# LEMC.net
KiCad netlist of a schematic drawn in Altium Designer
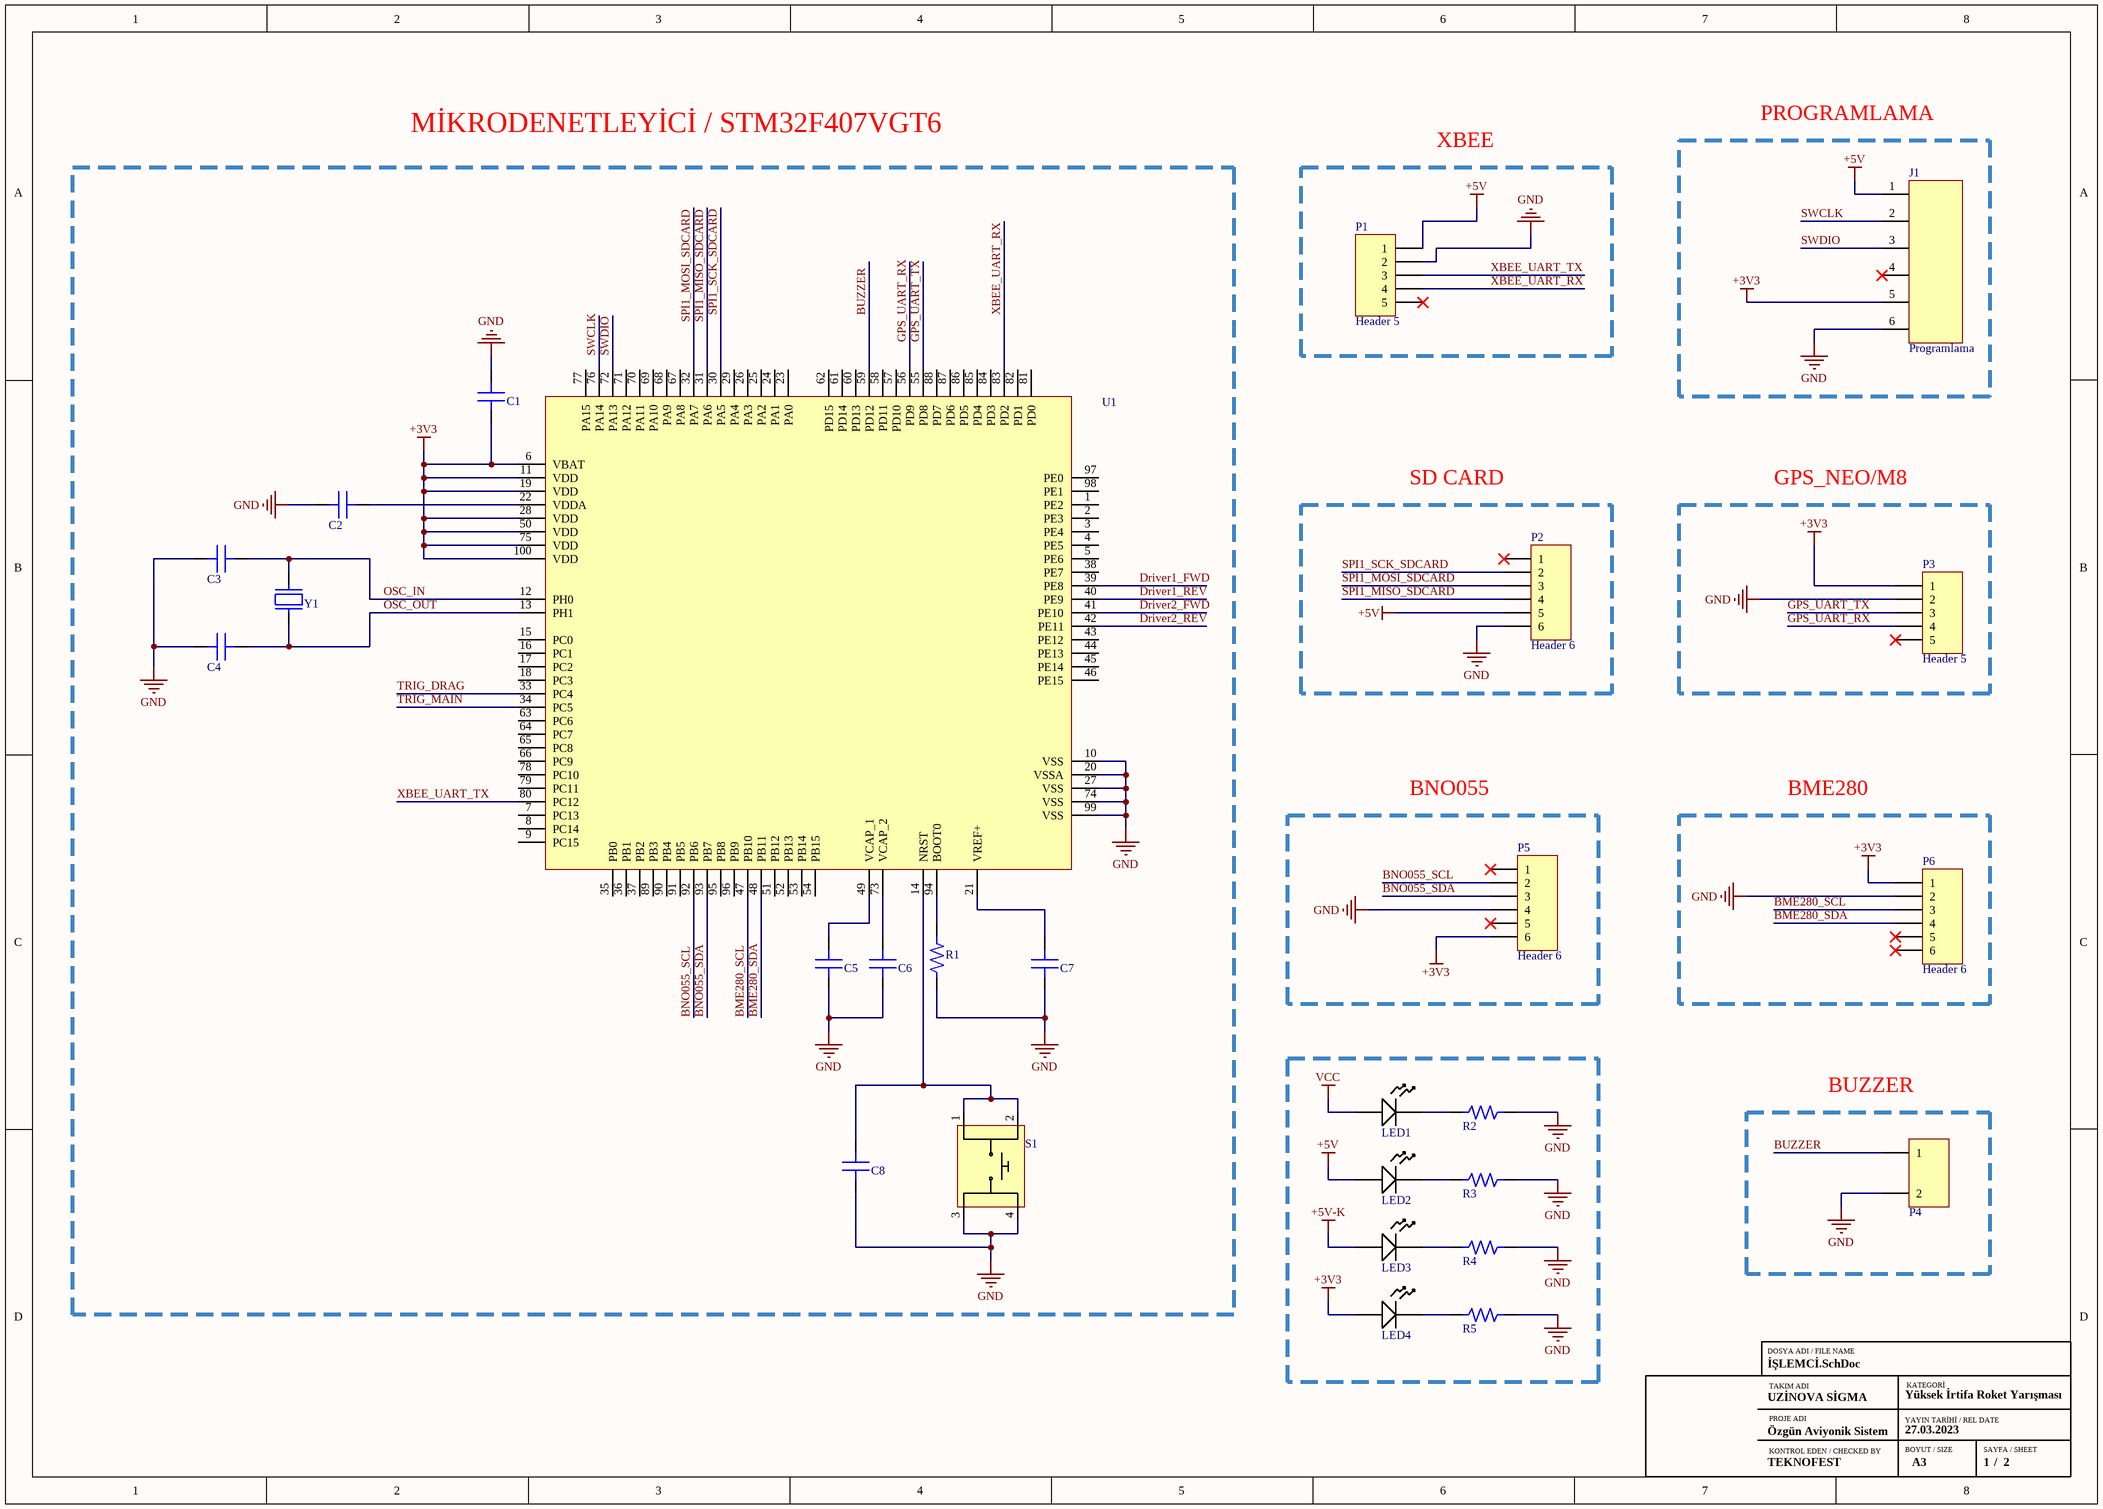
[diagram p0: İŞLEMCİ.SchDoc]

(export (version "E")
  (design (tool "Eeschema 10.0.6"))
  (components
    (comp (ref "C1")
      (value "CAP CER 1uF 0805")
      (footprint "CAP_0805")
      (libsource (lib "ROKET_LIBRARY") (part "CAP CER 1uF 0805"))
    )
    (comp (ref "C2")
      (value "CAP CER 10nF 0805")
      (footprint "CAP_0805")
      (libsource (lib "ROKET_LIBRARY") (part "CAP CER 10nF 0805"))
    )
    (comp (ref "C3")
      (value "CAP CER 20pF 0805")
      (footprint "CAP_0805")
      (libsource (lib "ROKET_LIBRARY") (part "CAP CER 20pF 0805"))
    )
    (comp (ref "C4")
      (value "CAP CER 20pF 0805")
      (footprint "CAP_0805")
      (libsource (lib "ROKET_LIBRARY") (part "CAP CER 20pF 0805"))
    )
    (comp (ref "C5")
      (value "CAP CER 2.2uF 0805")
      (footprint "CAP_0805")
      (libsource (lib "ROKET_LIBRARY") (part "CAP CER 2.2uF 0805"))
    )
    (comp (ref "C6")
      (value "CAP CER 2.2uF 0805")
      (footprint "CAP_0805")
      (libsource (lib "ROKET_LIBRARY") (part "CAP CER 2.2uF 0805"))
    )
    (comp (ref "C7")
      (value "CAP CER 10nF 0805")
      (footprint "CAP_0805")
      (libsource (lib "ROKET_LIBRARY") (part "CAP CER 10nF 0805"))
    )
    (comp (ref "C8")
      (value "CAP CER 0.1uF 0805")
      (footprint "CAP_0805")
      (libsource (lib "ROKET_LIBRARY") (part "CAP CER 0.1uF 0805"))
    )
    (comp (ref "J1")
      (value "Programlama")
      (footprint "PPTC061LFBN-RC")
      (libsource (lib "ROKET_LIBRARY") (part "Programlama"))
    )
    (comp (ref "LED1")
      (value "CMD17-21VRD/TR8")
      (footprint "LED RED_0805")
      (description "LED Uni-Color Red 640nm 2-Pin SMT T/R")
      (fields (field (name "MANUFACTURER") "VCC CHML"))
      (libsource (lib "ROKET_LIBRARY") (part "LED RED"))
    )
    (comp (ref "LED2")
      (value "CMD17-21VRD/TR8")
      (footprint "LED RED_0805")
      (description "LED Uni-Color Red 640nm 2-Pin SMT T/R")
      (fields (field (name "MANUFACTURER") "VCC CHML"))
      (libsource (lib "ROKET_LIBRARY") (part "LED RED"))
    )
    (comp (ref "LED3")
      (value "CMD17-21VRD/TR8")
      (footprint "LED RED_0805")
      (description "LED Uni-Color Red 640nm 2-Pin SMT T/R")
      (fields (field (name "MANUFACTURER") "VCC CHML"))
      (libsource (lib "ROKET_LIBRARY") (part "LED RED"))
    )
    (comp (ref "LED4")
      (value "CMD17-21VRD/TR8")
      (footprint "LED RED_0805")
      (description "LED Uni-Color Red 640nm 2-Pin SMT T/R")
      (fields (field (name "MANUFACTURER") "VCC CHML"))
      (libsource (lib "ROKET_LIBRARY") (part "LED RED"))
    )
    (comp (ref "P1")
      (value "Header 5")
      (footprint "HDR1X5")
      (description "Header, 5-Pin")
      (fields (field (name "PUBLISHER") "Altium Limited"))
      (libsource (lib "Miscellaneous Connectors") (part "Header 5"))
    )
    (comp (ref "P2")
      (value "Header 6")
      (footprint "HDR1X6")
      (description "Header, 6-Pin")
      (fields (field (name "PUBLISHER") "Altium Limited"))
      (libsource (lib "Miscellaneous Connectors") (part "Header 6"))
    )
    (comp (ref "P3")
      (value "Header 5")
      (footprint "HDR1X5")
      (description "Header, 5-Pin")
      (fields (field (name "PUBLISHER") "Altium Limited"))
      (libsource (lib "") (part "Header 5_1"))
    )
    (comp (ref "P4")
      (value "Yalancı Buzzer")
      (footprint "Yalancı Buzzer")
      (libsource (lib "ROKET_LIBRARY") (part "Yalancı Buzzer"))
    )
    (comp (ref "P5")
      (value "Header 6")
      (footprint "HDR1X6")
      (description "Header, 6-Pin")
      (fields (field (name "PUBLISHER") "Altium Limited"))
      (libsource (lib "Miscellaneous Connectors") (part "Header 6"))
    )
    (comp (ref "P6")
      (value "Header 6")
      (footprint "HDR1X6")
      (description "Header, 6-Pin")
      (fields (field (name "PUBLISHER") "Altium Limited"))
      (libsource (lib "Miscellaneous Connectors") (part "Header 6"))
    )
    (comp (ref "R1")
      (value "RES 10K OHM 0805")
      (footprint "RES_0805")
      (libsource (lib "ROKET_LIBRARY") (part "RES 10K OHM 0805"))
    )
    (comp (ref "R2")
      (value "RES 470 OHM 0805")
      (footprint "RES_0805")
      (libsource (lib "ROKET_LIBRARY") (part "RES 470 OHM 0805"))
    )
    (comp (ref "R3")
      (value "RES 470 OHM 0805")
      (footprint "RES_0805")
      (libsource (lib "ROKET_LIBRARY") (part "RES 470 OHM 0805"))
    )
    (comp (ref "R4")
      (value "RES 470 OHM 0805")
      (footprint "RES_0805")
      (libsource (lib "ROKET_LIBRARY") (part "RES 470 OHM 0805"))
    )
    (comp (ref "R5")
      (value "RES 470 OHM 0805")
      (footprint "RES_0805")
      (libsource (lib "ROKET_LIBRARY") (part "RES 470 OHM 0805"))
    )
    (comp (ref "S1")
      (value "PTS815 SJG 250 SMTR LFS")
      (footprint "BUTTON")
      (description "Switch Tactile N.O. SPST Button J-Bend 0.05A 12VDC 3.92N SMD T/R")
      (fields
        (field (name "MANUFACTURER") "ITT C&K")
        (field (name "MANUFACTURER PART NUMBER") "PTS815SJG250SMTRLFS")
      )
      (libsource (lib "ROKET_LIBRARY") (part "BUTTON"))
    )
    (comp (ref "U1")
      (value "STM32F407VGT6")
      (footprint "LQFP-100")
      (description "IC MCU 32BIT 1MB FLASH 100LQFP")
      (fields (field (name "MANUFACTURER") "STMicroelectronics"))
      (libsource (lib "ROKET_LIBRARY") (part "STM32F407VGT6"))
    )
    (comp (ref "Y1")
      (value "CRYSTAL 32.7680KHZ 12.5PF SMD")
      (footprint "CRYSTAL_ABS05")
      (description "Crystal 0.032768MHz ±20ppm (Tol) 12.5pF Flexural 90000Ohm 2-Pin CSMD T/R")
      (fields
        (field (name "MANUFACTURER") "Abracon")
        (field (name "MANUFACTURER PART NUMBER") "ABS05-32.768KHZ-T")
      )
      (libsource (lib "ROKET_LIBRARY") (part "CRYSTAL"))
    )
  )
  (nets
    (net (code "1") (name "+3V3") (class "Default")
      (node (ref "C1") (pin "1") (pinfunction "1_1") (pintype "passive"))
      (node (ref "J1") (pin "5") (pintype "passive"))
      (node (ref "LED4") (pin "1") (pinfunction "1_1") (pintype "passive"))
      (node (ref "P3") (pin "1") (pinfunction "1_1") (pintype "passive"))
      (node (ref "P5") (pin "6") (pinfunction "6_6") (pintype "passive"))
      (node (ref "P6") (pin "1") (pinfunction "1_1") (pintype "passive"))
      (node (ref "U1") (pin "100") (pinfunction "VDD_100") (pintype "passive"))
      (node (ref "U1") (pin "11") (pinfunction "VDD_11") (pintype "passive"))
      (node (ref "U1") (pin "19") (pinfunction "VDD_19") (pintype "passive"))
      (node (ref "U1") (pin "28") (pinfunction "VDD_28") (pintype "passive"))
      (node (ref "U1") (pin "50") (pinfunction "VDD_50") (pintype "passive"))
      (node (ref "U1") (pin "6") (pinfunction "VBAT_6") (pintype "passive"))
      (node (ref "U1") (pin "75") (pinfunction "VDD_75") (pintype "passive"))
    )
    (net (code "2") (name "+5V") (class "Default")
      (node (ref "J1") (pin "1") (pintype "passive"))
      (node (ref "LED2") (pin "1") (pinfunction "1_1") (pintype "passive"))
      (node (ref "P1") (pin "1") (pinfunction "1_1") (pintype "passive"))
      (node (ref "P2") (pin "5") (pinfunction "5_5") (pintype "passive"))
    )
    (net (code "3") (name "+5V-K") (class "Default")
      (node (ref "LED3") (pin "1") (pinfunction "1_1") (pintype "passive"))
    )
    (net (code "4") (name "/BME280_SCL") (class "Default")
      (node (ref "P6") (pin "3") (pinfunction "3_3") (pintype "passive"))
      (node (ref "U1") (pin "47") (pinfunction "PB10_47") (pintype "passive"))
    )
    (net (code "5") (name "/BME280_SDA") (class "Default")
      (node (ref "P6") (pin "4") (pinfunction "4_4") (pintype "passive"))
      (node (ref "U1") (pin "48") (pinfunction "PB11_48") (pintype "passive"))
    )
    (net (code "6") (name "/BNO055_SCL") (class "Default")
      (node (ref "P5") (pin "2") (pinfunction "2_2") (pintype "passive"))
      (node (ref "U1") (pin "92") (pinfunction "PB6_92") (pintype "passive"))
    )
    (net (code "7") (name "/BNO055_SDA") (class "Default")
      (node (ref "P5") (pin "3") (pinfunction "3_3") (pintype "passive"))
      (node (ref "U1") (pin "93") (pinfunction "PB7_93") (pintype "passive"))
    )
    (net (code "8") (name "/BUZZER") (class "Default")
      (node (ref "P4") (pin "1") (pinfunction "1_1") (pintype "passive"))
      (node (ref "U1") (pin "59") (pinfunction "PD12_59") (pintype "passive"))
    )
    (net (code "9") (name "/Driver1_FWD") (class "Default")
      (node (ref "U1") (pin "39") (pinfunction "PE8_39") (pintype "passive"))
    )
    (net (code "10") (name "/Driver1_REV") (class "Default")
      (node (ref "U1") (pin "40") (pinfunction "PE9_40") (pintype "passive"))
    )
    (net (code "11") (name "/Driver2_FWD") (class "Default")
      (node (ref "U1") (pin "41") (pinfunction "PE10_41") (pintype "passive"))
    )
    (net (code "12") (name "/Driver2_REV") (class "Default")
      (node (ref "U1") (pin "42") (pinfunction "PE11_42") (pintype "passive"))
    )
    (net (code "13") (name "/GPS_UART_RX") (class "Default")
      (node (ref "P3") (pin "4") (pinfunction "4_4") (pintype "passive"))
      (node (ref "U1") (pin "56") (pinfunction "PD9_56") (pintype "passive"))
    )
    (net (code "14") (name "/GPS_UART_TX") (class "Default")
      (node (ref "P3") (pin "3") (pinfunction "3_3") (pintype "passive"))
      (node (ref "U1") (pin "55") (pinfunction "PD8_55") (pintype "passive"))
    )
    (net (code "15") (name "/OSC_IN") (class "Default")
      (node (ref "C3") (pin "2") (pinfunction "2_2") (pintype "passive"))
      (node (ref "U1") (pin "12") (pinfunction "PH0_12") (pintype "passive"))
      (node (ref "Y1") (pin "2") (pinfunction "2_2") (pintype "passive"))
    )
    (net (code "16") (name "/OSC_OUT") (class "Default")
      (node (ref "C4") (pin "2") (pinfunction "2_2") (pintype "passive"))
      (node (ref "U1") (pin "13") (pinfunction "PH1_13") (pintype "passive"))
      (node (ref "Y1") (pin "1") (pinfunction "1_1") (pintype "passive"))
    )
    (net (code "17") (name "/SPI1_MISO_SDCARD") (class "Default")
      (node (ref "P2") (pin "4") (pinfunction "4_4") (pintype "passive"))
      (node (ref "U1") (pin "31") (pinfunction "PA6_31") (pintype "passive"))
    )
    (net (code "18") (name "/SPI1_MOSI_SDCARD") (class "Default")
      (node (ref "P2") (pin "3") (pinfunction "3_3") (pintype "passive"))
      (node (ref "U1") (pin "32") (pinfunction "PA7_32") (pintype "passive"))
    )
    (net (code "19") (name "/SPI1_SCK_SDCARD") (class "Default")
      (node (ref "P2") (pin "2") (pinfunction "2_2") (pintype "passive"))
      (node (ref "U1") (pin "30") (pinfunction "PA5_30") (pintype "passive"))
    )
    (net (code "20") (name "/SWCLK") (class "Default")
      (node (ref "J1") (pin "2") (pintype "passive"))
      (node (ref "U1") (pin "76") (pinfunction "PA14_76") (pintype "passive"))
    )
    (net (code "21") (name "/SWDIO") (class "Default")
      (node (ref "J1") (pin "3") (pintype "passive"))
      (node (ref "U1") (pin "72") (pinfunction "PA13_72") (pintype "passive"))
    )
    (net (code "22") (name "/TRIG_DRAG") (class "Default")
      (node (ref "U1") (pin "33") (pinfunction "PC4_33") (pintype "passive"))
    )
    (net (code "23") (name "/TRIG_MAIN") (class "Default")
      (node (ref "U1") (pin "34") (pinfunction "PC5_34") (pintype "passive"))
    )
    (net (code "24") (name "/XBEE_UART_RX") (class "Default")
      (node (ref "P1") (pin "4") (pinfunction "4_4") (pintype "passive"))
      (node (ref "U1") (pin "83") (pinfunction "PD2_83") (pintype "passive"))
    )
    (net (code "25") (name "/XBEE_UART_TX") (class "Default")
      (node (ref "P1") (pin "3") (pinfunction "3_3") (pintype "passive"))
      (node (ref "U1") (pin "80") (pinfunction "PC12_80") (pintype "passive"))
    )
    (net (code "26") (name "GND") (class "Default")
      (node (ref "C1") (pin "2") (pinfunction "2_2") (pintype "passive"))
      (node (ref "C2") (pin "1") (pinfunction "1_1") (pintype "passive"))
      (node (ref "C3") (pin "1") (pinfunction "1_1") (pintype "passive"))
      (node (ref "C4") (pin "1") (pinfunction "1_1") (pintype "passive"))
      (node (ref "C5") (pin "1") (pinfunction "1_1") (pintype "passive"))
      (node (ref "C6") (pin "1") (pinfunction "1_1") (pintype "passive"))
      (node (ref "C7") (pin "1") (pinfunction "1_1") (pintype "passive"))
      (node (ref "C8") (pin "1") (pinfunction "1_1") (pintype "passive"))
      (node (ref "J1") (pin "6") (pintype "passive"))
      (node (ref "P1") (pin "2") (pinfunction "2_2") (pintype "passive"))
      (node (ref "P2") (pin "6") (pinfunction "6_6") (pintype "passive"))
      (node (ref "P3") (pin "2") (pinfunction "2_2") (pintype "passive"))
      (node (ref "P4") (pin "2") (pinfunction "2_2") (pintype "passive"))
      (node (ref "P5") (pin "4") (pinfunction "4_4") (pintype "passive"))
      (node (ref "P6") (pin "2") (pinfunction "2_2") (pintype "passive"))
      (node (ref "R1") (pin "1") (pinfunction "1_1") (pintype "passive"))
      (node (ref "R2") (pin "2") (pinfunction "2_2") (pintype "passive"))
      (node (ref "R3") (pin "2") (pinfunction "2_2") (pintype "passive"))
      (node (ref "R4") (pin "2") (pinfunction "2_2") (pintype "passive"))
      (node (ref "R5") (pin "2") (pinfunction "2_2") (pintype "passive"))
      (node (ref "S1") (pin "3") (pinfunction "3_3") (pintype "passive"))
      (node (ref "S1") (pin "4") (pinfunction "4_4") (pintype "passive"))
      (node (ref "U1") (pin "10") (pinfunction "VSS_10") (pintype "passive"))
      (node (ref "U1") (pin "20") (pinfunction "VSSA_20") (pintype "passive"))
      (node (ref "U1") (pin "27") (pinfunction "VSS_27") (pintype "passive"))
      (node (ref "U1") (pin "74") (pinfunction "VSS_74") (pintype "passive"))
      (node (ref "U1") (pin "99") (pinfunction "VSS_99") (pintype "passive"))
    )
    (net (code "27") (name "Net-(LED1-Pad2)") (class "Default")
      (node (ref "LED1") (pin "2") (pinfunction "2_2") (pintype "passive"))
      (node (ref "R2") (pin "1") (pinfunction "1_1") (pintype "passive"))
    )
    (net (code "28") (name "Net-(LED2-Pad2)") (class "Default")
      (node (ref "LED2") (pin "2") (pinfunction "2_2") (pintype "passive"))
      (node (ref "R3") (pin "1") (pinfunction "1_1") (pintype "passive"))
    )
    (net (code "29") (name "Net-(LED3-Pad2)") (class "Default")
      (node (ref "LED3") (pin "2") (pinfunction "2_2") (pintype "passive"))
      (node (ref "R4") (pin "1") (pinfunction "1_1") (pintype "passive"))
    )
    (net (code "30") (name "Net-(LED4-Pad2)") (class "Default")
      (node (ref "LED4") (pin "2") (pinfunction "2_2") (pintype "passive"))
      (node (ref "R5") (pin "1") (pinfunction "1_1") (pintype "passive"))
    )
    (net (code "31") (name "Net-(U1-BOOT0)") (class "Default")
      (node (ref "R1") (pin "2") (pinfunction "2_2") (pintype "passive"))
      (node (ref "U1") (pin "94") (pinfunction "BOOT0_94") (pintype "passive"))
    )
    (net (code "32") (name "Net-(U1-NRST)") (class "Default")
      (node (ref "C8") (pin "2") (pinfunction "2_2") (pintype "passive"))
      (node (ref "S1") (pin "1") (pinfunction "1_1") (pintype "passive"))
      (node (ref "S1") (pin "2") (pinfunction "2_2") (pintype "passive"))
      (node (ref "U1") (pin "14") (pinfunction "NRST_14") (pintype "passive"))
    )
    (net (code "33") (name "Net-(U1-VCAP_1)") (class "Default")
      (node (ref "C5") (pin "2") (pinfunction "2_2") (pintype "passive"))
      (node (ref "U1") (pin "49") (pinfunction "VCAP_1_49") (pintype "passive"))
    )
    (net (code "34") (name "Net-(U1-VCAP_2)") (class "Default")
      (node (ref "C6") (pin "2") (pinfunction "2_2") (pintype "passive"))
      (node (ref "U1") (pin "73") (pinfunction "VCAP_2_73") (pintype "passive"))
    )
    (net (code "35") (name "Net-(U1-VDDA)") (class "Default")
      (node (ref "C2") (pin "2") (pinfunction "2_2") (pintype "passive"))
      (node (ref "U1") (pin "22") (pinfunction "VDDA_22") (pintype "passive"))
    )
    (net (code "36") (name "Net-(U1-VREF+)") (class "Default")
      (node (ref "C7") (pin "2") (pinfunction "2_2") (pintype "passive"))
      (node (ref "U1") (pin "21") (pinfunction "VREF+_21") (pintype "passive"))
    )
    (net (code "37") (name "VCC") (class "Default")
      (node (ref "LED1") (pin "1") (pinfunction "1_1") (pintype "passive"))
    )
    (net (code "38") (name "unconnected-(J1-Pad4)") (class "Default")
      (node (ref "J1") (pin "4") (pintype "passive+no_connect"))
    )
    (net (code "39") (name "unconnected-(P1-Pad5)") (class "Default")
      (node (ref "P1") (pin "5") (pinfunction "5_5") (pintype "passive+no_connect"))
    )
    (net (code "40") (name "unconnected-(P2-Pad1)") (class "Default")
      (node (ref "P2") (pin "1") (pinfunction "1_1") (pintype "passive+no_connect"))
    )
    (net (code "41") (name "unconnected-(P3-Pad5)") (class "Default")
      (node (ref "P3") (pin "5") (pinfunction "5_5") (pintype "passive+no_connect"))
    )
    (net (code "42") (name "unconnected-(P5-Pad1)") (class "Default")
      (node (ref "P5") (pin "1") (pinfunction "1_1") (pintype "passive+no_connect"))
    )
    (net (code "43") (name "unconnected-(P5-Pad5)") (class "Default")
      (node (ref "P5") (pin "5") (pinfunction "5_5") (pintype "passive+no_connect"))
    )
    (net (code "44") (name "unconnected-(P6-Pad5)") (class "Default")
      (node (ref "P6") (pin "5") (pinfunction "5_5") (pintype "passive+no_connect"))
    )
    (net (code "45") (name "unconnected-(P6-Pad6)") (class "Default")
      (node (ref "P6") (pin "6") (pinfunction "6_6") (pintype "passive+no_connect"))
    )
    (net (code "46") (name "unconnected-(U1-PA0-Pad23)") (class "Default")
      (node (ref "U1") (pin "23") (pinfunction "PA0_23") (pintype "passive"))
    )
    (net (code "47") (name "unconnected-(U1-PA1-Pad24)") (class "Default")
      (node (ref "U1") (pin "24") (pinfunction "PA1_24") (pintype "passive"))
    )
    (net (code "48") (name "unconnected-(U1-PA2-Pad25)") (class "Default")
      (node (ref "U1") (pin "25") (pinfunction "PA2_25") (pintype "passive"))
    )
    (net (code "49") (name "unconnected-(U1-PA3-Pad26)") (class "Default")
      (node (ref "U1") (pin "26") (pinfunction "PA3_26") (pintype "passive"))
    )
    (net (code "50") (name "unconnected-(U1-PA4-Pad29)") (class "Default")
      (node (ref "U1") (pin "29") (pinfunction "PA4_29") (pintype "passive"))
    )
    (net (code "51") (name "unconnected-(U1-PA8-Pad67)") (class "Default")
      (node (ref "U1") (pin "67") (pinfunction "PA8_67") (pintype "passive"))
    )
    (net (code "52") (name "unconnected-(U1-PA9-Pad68)") (class "Default")
      (node (ref "U1") (pin "68") (pinfunction "PA9_68") (pintype "passive"))
    )
    (net (code "53") (name "unconnected-(U1-PA10-Pad69)") (class "Default")
      (node (ref "U1") (pin "69") (pinfunction "PA10_69") (pintype "passive"))
    )
    (net (code "54") (name "unconnected-(U1-PA11-Pad70)") (class "Default")
      (node (ref "U1") (pin "70") (pinfunction "PA11_70") (pintype "passive"))
    )
    (net (code "55") (name "unconnected-(U1-PA12-Pad71)") (class "Default")
      (node (ref "U1") (pin "71") (pinfunction "PA12_71") (pintype "passive"))
    )
    (net (code "56") (name "unconnected-(U1-PA15-Pad77)") (class "Default")
      (node (ref "U1") (pin "77") (pinfunction "PA15_77") (pintype "passive"))
    )
    (net (code "57") (name "unconnected-(U1-PB0-Pad35)") (class "Default")
      (node (ref "U1") (pin "35") (pinfunction "PB0_35") (pintype "passive"))
    )
    (net (code "58") (name "unconnected-(U1-PB1-Pad36)") (class "Default")
      (node (ref "U1") (pin "36") (pinfunction "PB1_36") (pintype "passive"))
    )
    (net (code "59") (name "unconnected-(U1-PB2-Pad37)") (class "Default")
      (node (ref "U1") (pin "37") (pinfunction "PB2_37") (pintype "passive"))
    )
    (net (code "60") (name "unconnected-(U1-PB3-Pad89)") (class "Default")
      (node (ref "U1") (pin "89") (pinfunction "PB3_89") (pintype "passive"))
    )
    (net (code "61") (name "unconnected-(U1-PB4-Pad90)") (class "Default")
      (node (ref "U1") (pin "90") (pinfunction "PB4_90") (pintype "passive"))
    )
    (net (code "62") (name "unconnected-(U1-PB5-Pad91)") (class "Default")
      (node (ref "U1") (pin "91") (pinfunction "PB5_91") (pintype "passive"))
    )
    (net (code "63") (name "unconnected-(U1-PB8-Pad95)") (class "Default")
      (node (ref "U1") (pin "95") (pinfunction "PB8_95") (pintype "passive"))
    )
    (net (code "64") (name "unconnected-(U1-PB9-Pad96)") (class "Default")
      (node (ref "U1") (pin "96") (pinfunction "PB9_96") (pintype "passive"))
    )
    (net (code "65") (name "unconnected-(U1-PB12-Pad51)") (class "Default")
      (node (ref "U1") (pin "51") (pinfunction "PB12_51") (pintype "passive"))
    )
    (net (code "66") (name "unconnected-(U1-PB13-Pad52)") (class "Default")
      (node (ref "U1") (pin "52") (pinfunction "PB13_52") (pintype "passive"))
    )
    (net (code "67") (name "unconnected-(U1-PB14-Pad53)") (class "Default")
      (node (ref "U1") (pin "53") (pinfunction "PB14_53") (pintype "passive"))
    )
    (net (code "68") (name "unconnected-(U1-PB15-Pad54)") (class "Default")
      (node (ref "U1") (pin "54") (pinfunction "PB15_54") (pintype "passive"))
    )
    (net (code "69") (name "unconnected-(U1-PC0-Pad15)") (class "Default")
      (node (ref "U1") (pin "15") (pinfunction "PC0_15") (pintype "passive"))
    )
    (net (code "70") (name "unconnected-(U1-PC1-Pad16)") (class "Default")
      (node (ref "U1") (pin "16") (pinfunction "PC1_16") (pintype "passive"))
    )
    (net (code "71") (name "unconnected-(U1-PC2-Pad17)") (class "Default")
      (node (ref "U1") (pin "17") (pinfunction "PC2_17") (pintype "passive"))
    )
    (net (code "72") (name "unconnected-(U1-PC3-Pad18)") (class "Default")
      (node (ref "U1") (pin "18") (pinfunction "PC3_18") (pintype "passive"))
    )
    (net (code "73") (name "unconnected-(U1-PC6-Pad63)") (class "Default")
      (node (ref "U1") (pin "63") (pinfunction "PC6_63") (pintype "passive"))
    )
    (net (code "74") (name "unconnected-(U1-PC7-Pad64)") (class "Default")
      (node (ref "U1") (pin "64") (pinfunction "PC7_64") (pintype "passive"))
    )
    (net (code "75") (name "unconnected-(U1-PC8-Pad65)") (class "Default")
      (node (ref "U1") (pin "65") (pinfunction "PC8_65") (pintype "passive"))
    )
    (net (code "76") (name "unconnected-(U1-PC9-Pad66)") (class "Default")
      (node (ref "U1") (pin "66") (pinfunction "PC9_66") (pintype "passive"))
    )
    (net (code "77") (name "unconnected-(U1-PC10-Pad78)") (class "Default")
      (node (ref "U1") (pin "78") (pinfunction "PC10_78") (pintype "passive"))
    )
    (net (code "78") (name "unconnected-(U1-PC11-Pad79)") (class "Default")
      (node (ref "U1") (pin "79") (pinfunction "PC11_79") (pintype "passive"))
    )
    (net (code "79") (name "unconnected-(U1-PC13-Pad7)") (class "Default")
      (node (ref "U1") (pin "7") (pinfunction "PC13_7") (pintype "passive"))
    )
    (net (code "80") (name "unconnected-(U1-PC14-Pad8)") (class "Default")
      (node (ref "U1") (pin "8") (pinfunction "PC14_8") (pintype "passive"))
    )
    (net (code "81") (name "unconnected-(U1-PC15-Pad9)") (class "Default")
      (node (ref "U1") (pin "9") (pinfunction "PC15_9") (pintype "passive"))
    )
    (net (code "82") (name "unconnected-(U1-PD0-Pad81)") (class "Default")
      (node (ref "U1") (pin "81") (pinfunction "PD0_81") (pintype "passive"))
    )
    (net (code "83") (name "unconnected-(U1-PD1-Pad82)") (class "Default")
      (node (ref "U1") (pin "82") (pinfunction "PD1_82") (pintype "passive"))
    )
    (net (code "84") (name "unconnected-(U1-PD3-Pad84)") (class "Default")
      (node (ref "U1") (pin "84") (pinfunction "PD3_84") (pintype "passive"))
    )
    (net (code "85") (name "unconnected-(U1-PD4-Pad85)") (class "Default")
      (node (ref "U1") (pin "85") (pinfunction "PD4_85") (pintype "passive"))
    )
    (net (code "86") (name "unconnected-(U1-PD5-Pad86)") (class "Default")
      (node (ref "U1") (pin "86") (pinfunction "PD5_86") (pintype "passive"))
    )
    (net (code "87") (name "unconnected-(U1-PD6-Pad87)") (class "Default")
      (node (ref "U1") (pin "87") (pinfunction "PD6_87") (pintype "passive"))
    )
    (net (code "88") (name "unconnected-(U1-PD7-Pad88)") (class "Default")
      (node (ref "U1") (pin "88") (pinfunction "PD7_88") (pintype "passive"))
    )
    (net (code "89") (name "unconnected-(U1-PD10-Pad57)") (class "Default")
      (node (ref "U1") (pin "57") (pinfunction "PD10_57") (pintype "passive"))
    )
    (net (code "90") (name "unconnected-(U1-PD11-Pad58)") (class "Default")
      (node (ref "U1") (pin "58") (pinfunction "PD11_58") (pintype "passive"))
    )
    (net (code "91") (name "unconnected-(U1-PD13-Pad60)") (class "Default")
      (node (ref "U1") (pin "60") (pinfunction "PD13_60") (pintype "passive"))
    )
    (net (code "92") (name "unconnected-(U1-PD14-Pad61)") (class "Default")
      (node (ref "U1") (pin "61") (pinfunction "PD14_61") (pintype "passive"))
    )
    (net (code "93") (name "unconnected-(U1-PD15-Pad62)") (class "Default")
      (node (ref "U1") (pin "62") (pinfunction "PD15_62") (pintype "passive"))
    )
    (net (code "94") (name "unconnected-(U1-PE0-Pad97)") (class "Default")
      (node (ref "U1") (pin "97") (pinfunction "PE0_97") (pintype "passive"))
    )
    (net (code "95") (name "unconnected-(U1-PE1-Pad98)") (class "Default")
      (node (ref "U1") (pin "98") (pinfunction "PE1_98") (pintype "passive"))
    )
    (net (code "96") (name "unconnected-(U1-PE2-Pad1)") (class "Default")
      (node (ref "U1") (pin "1") (pinfunction "PE2_1") (pintype "passive"))
    )
    (net (code "97") (name "unconnected-(U1-PE3-Pad2)") (class "Default")
      (node (ref "U1") (pin "2") (pinfunction "PE3_2") (pintype "passive"))
    )
    (net (code "98") (name "unconnected-(U1-PE4-Pad3)") (class "Default")
      (node (ref "U1") (pin "3") (pinfunction "PE4_3") (pintype "passive"))
    )
    (net (code "99") (name "unconnected-(U1-PE5-Pad4)") (class "Default")
      (node (ref "U1") (pin "4") (pinfunction "PE5_4") (pintype "passive"))
    )
    (net (code "100") (name "unconnected-(U1-PE6-Pad5)") (class "Default")
      (node (ref "U1") (pin "5") (pinfunction "PE6_5") (pintype "passive"))
    )
    (net (code "101") (name "unconnected-(U1-PE7-Pad38)") (class "Default")
      (node (ref "U1") (pin "38") (pinfunction "PE7_38") (pintype "passive"))
    )
    (net (code "102") (name "unconnected-(U1-PE12-Pad43)") (class "Default")
      (node (ref "U1") (pin "43") (pinfunction "PE12_43") (pintype "passive"))
    )
    (net (code "103") (name "unconnected-(U1-PE13-Pad44)") (class "Default")
      (node (ref "U1") (pin "44") (pinfunction "PE13_44") (pintype "passive"))
    )
    (net (code "104") (name "unconnected-(U1-PE14-Pad45)") (class "Default")
      (node (ref "U1") (pin "45") (pinfunction "PE14_45") (pintype "passive"))
    )
    (net (code "105") (name "unconnected-(U1-PE15-Pad46)") (class "Default")
      (node (ref "U1") (pin "46") (pinfunction "PE15_46") (pintype "passive"))
    )
  )
)
